# Sheet1.net
KiCad netlist of a schematic drawn in Altium Designer
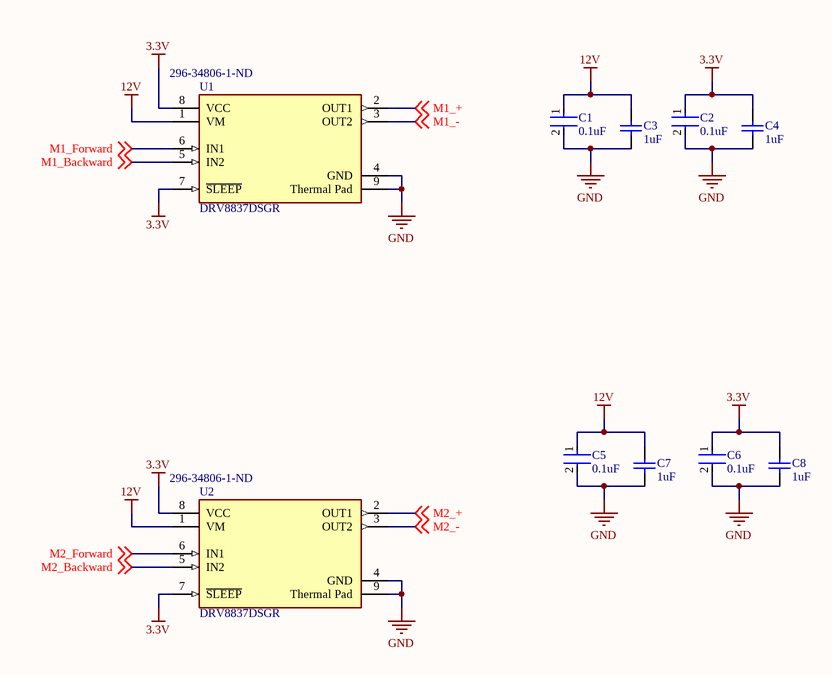
[diagram p0: Sheet1.SchDoc]

(export (version "E")
  (design (tool "Eeschema 10.0.6"))
  (components
    (comp (ref "C1")
      (value "0.1uF")
      (footprint "FP-CC0805-0_85-MFG")
      (description "CAP CER 0.1UF 25V X7R 0805")
      (fields (field (name "MANUFACTURER PART NUMBER") "CC0805KRX7R8BB104") (field (name "TOLERANCE") "0.1"))
      (libsource (lib "Altium Content Vault") (part "11868f565c42a9108669ba33697ecf6"))
    )
    (comp (ref "C2")
      (value "0.1uF")
      (footprint "FP-CC0805-0_85-MFG")
      (description "CAP CER 0.1UF 25V X7R 0805")
      (fields (field (name "MANUFACTURER PART NUMBER") "CC0805KRX7R8BB104") (field (name "TOLERANCE") "0.1"))
      (libsource (lib "Altium Content Vault") (part "11868f565c42a9108669ba33697ecf6"))
    )
    (comp (ref "C3")
      (value "1uF")
      (footprint "CAPC2013X145X50ML20T25")
      (fields
        (field (name "PART NUMBER") "CC0805ZRY5V8BB105")
        (field (name "MANUFACTURER") "Yageo")
        (field (name "TOLERANCE") "80%")
      )
      (libsource (lib "Altium Content Vault") (part "CAP"))
    )
    (comp (ref "C4")
      (value "1uF")
      (footprint "CAPC2013X145X50ML20T25")
      (fields
        (field (name "PART NUMBER") "CC0805ZRY5V8BB105")
        (field (name "MANUFACTURER") "Yageo")
        (field (name "TOLERANCE") "80%")
      )
      (libsource (lib "Altium Content Vault") (part "CAP"))
    )
    (comp (ref "C5")
      (value "0.1uF")
      (footprint "FP-CC0805-0_85-MFG")
      (description "CAP CER 0.1UF 25V X7R 0805")
      (fields (field (name "MANUFACTURER PART NUMBER") "CC0805KRX7R8BB104") (field (name "TOLERANCE") "0.1"))
      (libsource (lib "Altium Content Vault") (part "11868f565c42a9108669ba33697ecf6"))
    )
    (comp (ref "C6")
      (value "0.1uF")
      (footprint "FP-CC0805-0_85-MFG")
      (description "CAP CER 0.1UF 25V X7R 0805")
      (fields (field (name "MANUFACTURER PART NUMBER") "CC0805KRX7R8BB104") (field (name "TOLERANCE") "0.1"))
      (libsource (lib "Altium Content Vault") (part "11868f565c42a9108669ba33697ecf6"))
    )
    (comp (ref "C7")
      (value "1uF")
      (footprint "CAPC2013X145X50ML20T25")
      (fields
        (field (name "PART NUMBER") "CC0805ZRY5V8BB105")
        (field (name "MANUFACTURER") "Yageo")
        (field (name "TOLERANCE") "80%")
      )
      (libsource (lib "Altium Content Vault") (part "CAP"))
    )
    (comp (ref "C8")
      (value "1uF")
      (footprint "CAPC2013X145X50ML20T25")
      (fields
        (field (name "PART NUMBER") "CC0805ZRY5V8BB105")
        (field (name "MANUFACTURER") "Yageo")
        (field (name "TOLERANCE") "80%")
      )
      (libsource (lib "Altium Content Vault") (part "CAP"))
    )
    (comp (ref "U1")
      (value "DRV8837DSGR")
      (footprint "FP-DSG0008A-MFG")
      (description "IC MOTOR DRIVER PAR 8WSON")
      (fields
        (field (name "MANUFACTURER") "Texas Instruments")
        (field (name "OCTOPART") "https://octopart.com/drv8837dsgr-texas+instruments-23786726")
        (field (name "SUPPLIER PART NUMBER 1") "296-34806-1-ND")
      )
      (libsource (lib "Altium Content Vault") (part "0edabe62f55b79d65ef7cb8a22a7164"))
    )
    (comp (ref "U2")
      (value "DRV8837DSGR")
      (footprint "FP-DSG0008A-MFG")
      (description "IC MOTOR DRIVER PAR 8WSON")
      (fields
        (field (name "MANUFACTURER") "Texas Instruments")
        (field (name "OCTOPART") "https://octopart.com/drv8837dsgr-texas+instruments-23786726")
        (field (name "SUPPLIER PART NUMBER 1") "296-34806-1-ND")
      )
      (libsource (lib "Altium Content Vault") (part "0edabe62f55b79d65ef7cb8a22a7164"))
    )
  )
  (nets
    (net (code "1") (name "3.3V") (class "Default")
      (node (ref "C2") (pin "1") (pinfunction "1_1") (pintype "passive"))
      (node (ref "C4") (pin "2") (pinfunction "2_2") (pintype "passive"))
      (node (ref "C6") (pin "1") (pinfunction "1_1") (pintype "passive"))
      (node (ref "C8") (pin "2") (pinfunction "2_2") (pintype "passive"))
      (node (ref "U1") (pin "7") (pinfunction "~{SLEEP}_7") (pintype "input"))
      (node (ref "U1") (pin "8") (pinfunction "VCC_8") (pintype "power_in"))
      (node (ref "U2") (pin "7") (pinfunction "~{SLEEP}_7") (pintype "input"))
      (node (ref "U2") (pin "8") (pinfunction "VCC_8") (pintype "power_in"))
    )
    (net (code "2") (name "12V") (class "Default")
      (node (ref "C1") (pin "1") (pinfunction "1_1") (pintype "passive"))
      (node (ref "C3") (pin "2") (pinfunction "2_2") (pintype "passive"))
      (node (ref "C5") (pin "1") (pinfunction "1_1") (pintype "passive"))
      (node (ref "C7") (pin "2") (pinfunction "2_2") (pintype "passive"))
      (node (ref "U1") (pin "1") (pinfunction "VM_1") (pintype "power_in"))
      (node (ref "U2") (pin "1") (pinfunction "VM_1") (pintype "power_in"))
    )
    (net (code "3") (name "GND") (class "Default")
      (node (ref "C1") (pin "2") (pinfunction "2_2") (pintype "passive"))
      (node (ref "C2") (pin "2") (pinfunction "2_2") (pintype "passive"))
      (node (ref "C3") (pin "1") (pinfunction "1_1") (pintype "passive"))
      (node (ref "C4") (pin "1") (pinfunction "1_1") (pintype "passive"))
      (node (ref "C5") (pin "2") (pinfunction "2_2") (pintype "passive"))
      (node (ref "C6") (pin "2") (pinfunction "2_2") (pintype "passive"))
      (node (ref "C7") (pin "1") (pinfunction "1_1") (pintype "passive"))
      (node (ref "C8") (pin "1") (pinfunction "1_1") (pintype "passive"))
      (node (ref "U1") (pin "4") (pinfunction "GND_4") (pintype "power_in"))
      (node (ref "U1") (pin "9") (pinfunction "Thermal_Pad_9") (pintype "power_in"))
      (node (ref "U2") (pin "4") (pinfunction "GND_4") (pintype "power_in"))
      (node (ref "U2") (pin "9") (pinfunction "Thermal_Pad_9") (pintype "power_in"))
    )
    (net (code "4") (name "M1_+") (class "Default")
      (node (ref "U1") (pin "2") (pinfunction "OUT1_2") (pintype "output"))
    )
    (net (code "5") (name "M1_-") (class "Default")
      (node (ref "U1") (pin "3") (pinfunction "OUT2_3") (pintype "output"))
    )
    (net (code "6") (name "M1_Backward") (class "Default")
      (node (ref "U1") (pin "5") (pinfunction "IN2_5") (pintype "input"))
    )
    (net (code "7") (name "M1_Forward") (class "Default")
      (node (ref "U1") (pin "6") (pinfunction "IN1_6") (pintype "input"))
    )
    (net (code "8") (name "M2_+") (class "Default")
      (node (ref "U2") (pin "2") (pinfunction "OUT1_2") (pintype "output"))
    )
    (net (code "9") (name "M2_-") (class "Default")
      (node (ref "U2") (pin "3") (pinfunction "OUT2_3") (pintype "output"))
    )
    (net (code "10") (name "M2_Backward") (class "Default")
      (node (ref "U2") (pin "5") (pinfunction "IN2_5") (pintype "input"))
    )
    (net (code "11") (name "M2_Forward") (class "Default")
      (node (ref "U2") (pin "6") (pinfunction "IN1_6") (pintype "input"))
    )
  )
)
